# llrf_fmc_ext_male.net
KiCad netlist of a schematic drawn in Altium Designer
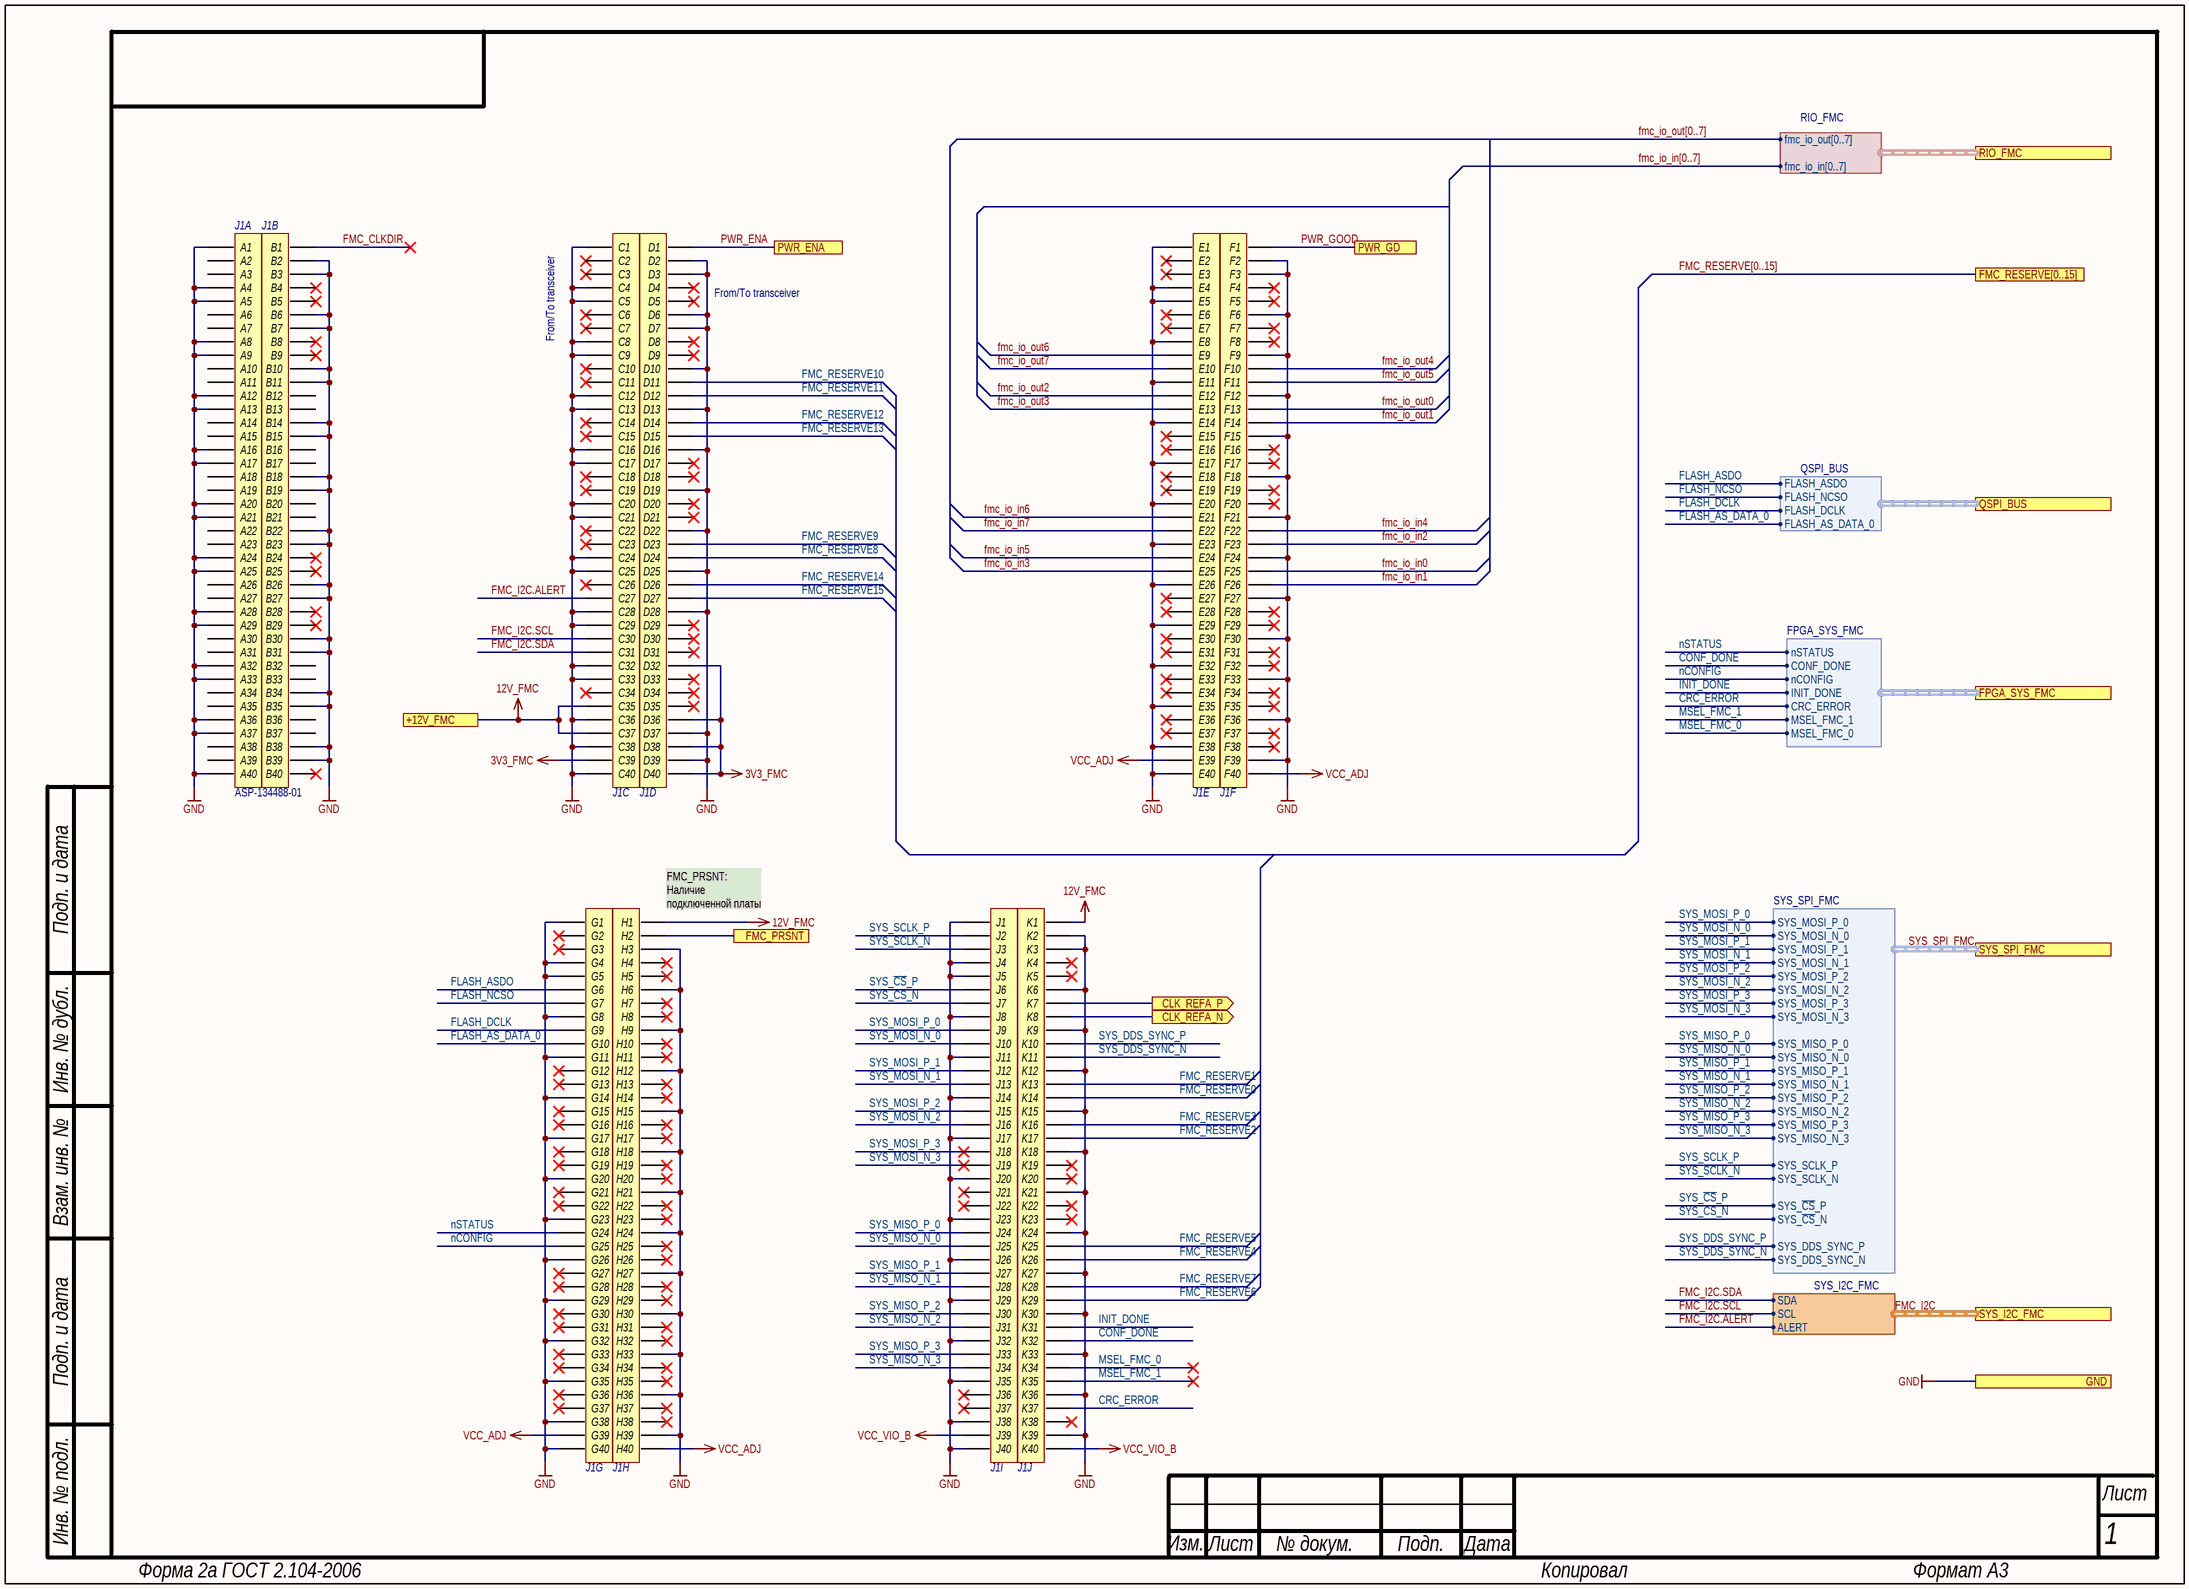
[diagram p0: llrf_fmc_ext_male.SchDoc]

(export (version "E")
  (design (tool "Eeschema 10.0.6"))
  (components
    (comp (ref "J1")
      (value "ASP-134488-01")
      (footprint "ASP-134488-01")
      (description "Socket Array Assembly, Surface Mount, 0.050\" Pitch, 400 Pins")
      (fields
        (field (name "MANUFACTURER") "SAMTEC")
        (field (name "НАИМЕНОВАНИЕ") "ASP-134488-01")
        (field (name "CREATED") "March 24, 2015 - Wendy Xin")
      )
      (libsource (lib "Connector") (part "ASP-134488-01"))
    )
  )
  (nets
    (net (code "6") (name "/CLK_REFA_N") (class "Default")
      (node (ref "J1") (pin "K8") (pinfunction "K8_K8") (pintype "passive"))
    )
    (net (code "7") (name "/CLK_REFA_P") (class "Default")
      (node (ref "J1") (pin "K7") (pinfunction "K7_K7") (pintype "passive"))
    )
    (net (code "8") (name "/CONF_DONE") (class "Default")
      (node (ref "J1") (pin "K32") (pinfunction "K32_K32") (pintype "passive"))
    )
    (net (code "9") (name "/CRC_ERROR") (class "Default")
      (node (ref "J1") (pin "K37") (pinfunction "K37_K37") (pintype "passive"))
    )
    (net (code "10") (name "/FLASH_ASDO") (class "Default")
      (node (ref "J1") (pin "G6") (pinfunction "G6_G6") (pintype "passive"))
    )
    (net (code "11") (name "/FLASH_AS_DATA_0") (class "Default")
      (node (ref "J1") (pin "G10") (pinfunction "G10_G10") (pintype "passive"))
    )
    (net (code "12") (name "/FLASH_DCLK") (class "Default")
      (node (ref "J1") (pin "G9") (pinfunction "G9_G9") (pintype "passive"))
    )
    (net (code "13") (name "/FLASH_NCSO") (class "Default")
      (node (ref "J1") (pin "G7") (pinfunction "G7_G7") (pintype "passive"))
    )
    (net (code "14") (name "/FMC_CLKDIR") (class "Default")
      (node (ref "J1") (pin "B1") (pinfunction "B1_B1") (pintype "passive+no_connect"))
    )
    (net (code "15") (name "/FMC_I2C.ALERT") (class "Default")
      (node (ref "J1") (pin "C27") (pinfunction "C27_C27") (pintype "passive"))
    )
    (net (code "16") (name "/FMC_I2C.SCL") (class "Default")
      (node (ref "J1") (pin "C30") (pinfunction "C30_C30") (pintype "passive"))
    )
    (net (code "17") (name "/FMC_I2C.SDA") (class "Default")
      (node (ref "J1") (pin "C31") (pinfunction "C31_C31") (pintype "passive"))
    )
    (net (code "19") (name "/FMC_PRSNT") (class "Default")
      (node (ref "J1") (pin "H2") (pinfunction "H2_H2") (pintype "passive"))
    )
    (net (code "20") (name "/FMC_RESERVE0") (class "Default")
      (node (ref "J1") (pin "K14") (pinfunction "K14_K14") (pintype "passive"))
    )
    (net (code "21") (name "/FMC_RESERVE1") (class "Default")
      (node (ref "J1") (pin "K13") (pinfunction "K13_K13") (pintype "passive"))
    )
    (net (code "22") (name "/FMC_RESERVE2") (class "Default")
      (node (ref "J1") (pin "K17") (pinfunction "K17_K17") (pintype "passive"))
    )
    (net (code "23") (name "/FMC_RESERVE3") (class "Default")
      (node (ref "J1") (pin "K16") (pinfunction "K16_K16") (pintype "passive"))
    )
    (net (code "24") (name "/FMC_RESERVE4") (class "Default")
      (node (ref "J1") (pin "K26") (pinfunction "K26_K26") (pintype "passive"))
    )
    (net (code "25") (name "/FMC_RESERVE5") (class "Default")
      (node (ref "J1") (pin "K25") (pinfunction "K25_K25") (pintype "passive"))
    )
    (net (code "26") (name "/FMC_RESERVE6") (class "Default")
      (node (ref "J1") (pin "K29") (pinfunction "K29_K29") (pintype "passive"))
    )
    (net (code "27") (name "/FMC_RESERVE7") (class "Default")
      (node (ref "J1") (pin "K28") (pinfunction "K28_K28") (pintype "passive"))
    )
    (net (code "28") (name "/FMC_RESERVE8") (class "Default")
      (node (ref "J1") (pin "D24") (pinfunction "D24_D24") (pintype "passive"))
    )
    (net (code "29") (name "/FMC_RESERVE9") (class "Default")
      (node (ref "J1") (pin "D23") (pinfunction "D23_D23") (pintype "passive"))
    )
    (net (code "30") (name "/FMC_RESERVE10") (class "Default")
      (node (ref "J1") (pin "D11") (pinfunction "D11_D11") (pintype "passive"))
    )
    (net (code "31") (name "/FMC_RESERVE11") (class "Default")
      (node (ref "J1") (pin "D12") (pinfunction "D12_D12") (pintype "passive"))
    )
    (net (code "32") (name "/FMC_RESERVE12") (class "Default")
      (node (ref "J1") (pin "D14") (pinfunction "D14_D14") (pintype "passive"))
    )
    (net (code "33") (name "/FMC_RESERVE13") (class "Default")
      (node (ref "J1") (pin "D15") (pinfunction "D15_D15") (pintype "passive"))
    )
    (net (code "34") (name "/FMC_RESERVE14") (class "Default")
      (node (ref "J1") (pin "D26") (pinfunction "D26_D26") (pintype "passive"))
    )
    (net (code "35") (name "/FMC_RESERVE15") (class "Default")
      (node (ref "J1") (pin "D27") (pinfunction "D27_D27") (pintype "passive"))
    )
    (net (code "37") (name "/INIT_DONE") (class "Default")
      (node (ref "J1") (pin "K31") (pinfunction "K31_K31") (pintype "passive"))
    )
    (net (code "38") (name "/MSEL_FMC_0") (class "Default")
      (node (ref "J1") (pin "K34") (pinfunction "K34_K34") (pintype "passive+no_connect"))
    )
    (net (code "39") (name "/MSEL_FMC_1") (class "Default")
      (node (ref "J1") (pin "K35") (pinfunction "K35_K35") (pintype "passive+no_connect"))
    )
    (net (code "40") (name "/PWR_ENA") (class "Default")
      (node (ref "J1") (pin "D1") (pinfunction "D1_D1") (pintype "passive"))
    )
    (net (code "41") (name "/PWR_GOOD") (class "Default")
      (node (ref "J1") (pin "F1") (pinfunction "F1_F1") (pintype "passive"))
    )
    (net (code "43") (name "/SYS_DDS_SYNC_N") (class "Default")
      (node (ref "J1") (pin "K11") (pinfunction "K11_K11") (pintype "passive"))
    )
    (net (code "44") (name "/SYS_DDS_SYNC_P") (class "Default")
      (node (ref "J1") (pin "K10") (pinfunction "K10_K10") (pintype "passive"))
    )
    (net (code "45") (name "/SYS_MISO_N_0") (class "Default")
      (node (ref "J1") (pin "J25") (pinfunction "J25_J25") (pintype "passive"))
    )
    (net (code "46") (name "/SYS_MISO_N_1") (class "Default")
      (node (ref "J1") (pin "J28") (pinfunction "J28_J28") (pintype "passive"))
    )
    (net (code "47") (name "/SYS_MISO_N_2") (class "Default")
      (node (ref "J1") (pin "J31") (pinfunction "J31_J31") (pintype "passive"))
    )
    (net (code "48") (name "/SYS_MISO_N_3") (class "Default")
      (node (ref "J1") (pin "J34") (pinfunction "J34_J34") (pintype "passive"))
    )
    (net (code "49") (name "/SYS_MISO_P_0") (class "Default")
      (node (ref "J1") (pin "J24") (pinfunction "J24_J24") (pintype "passive"))
    )
    (net (code "50") (name "/SYS_MISO_P_1") (class "Default")
      (node (ref "J1") (pin "J27") (pinfunction "J27_J27") (pintype "passive"))
    )
    (net (code "51") (name "/SYS_MISO_P_2") (class "Default")
      (node (ref "J1") (pin "J30") (pinfunction "J30_J30") (pintype "passive"))
    )
    (net (code "52") (name "/SYS_MISO_P_3") (class "Default")
      (node (ref "J1") (pin "J33") (pinfunction "J33_J33") (pintype "passive"))
    )
    (net (code "53") (name "/SYS_MOSI_N_0") (class "Default")
      (node (ref "J1") (pin "J10") (pinfunction "J10_J10") (pintype "passive"))
    )
    (net (code "54") (name "/SYS_MOSI_N_1") (class "Default")
      (node (ref "J1") (pin "J13") (pinfunction "J13_J13") (pintype "passive"))
    )
    (net (code "55") (name "/SYS_MOSI_N_2") (class "Default")
      (node (ref "J1") (pin "J16") (pinfunction "J16_J16") (pintype "passive"))
    )
    (net (code "56") (name "/SYS_MOSI_N_3") (class "Default")
      (node (ref "J1") (pin "J19") (pinfunction "J19_J19") (pintype "passive"))
    )
    (net (code "57") (name "/SYS_MOSI_P_0") (class "Default")
      (node (ref "J1") (pin "J9") (pinfunction "J9_J9") (pintype "passive"))
    )
    (net (code "58") (name "/SYS_MOSI_P_1") (class "Default")
      (node (ref "J1") (pin "J12") (pinfunction "J12_J12") (pintype "passive"))
    )
    (net (code "59") (name "/SYS_MOSI_P_2") (class "Default")
      (node (ref "J1") (pin "J15") (pinfunction "J15_J15") (pintype "passive"))
    )
    (net (code "60") (name "/SYS_MOSI_P_3") (class "Default")
      (node (ref "J1") (pin "J18") (pinfunction "J18_J18") (pintype "passive"))
    )
    (net (code "61") (name "/SYS_SCLK_N") (class "Default")
      (node (ref "J1") (pin "J3") (pinfunction "J3_J3") (pintype "passive"))
    )
    (net (code "62") (name "/SYS_SCLK_P") (class "Default")
      (node (ref "J1") (pin "J2") (pinfunction "J2_J2") (pintype "passive"))
    )
    (net (code "64") (name "/SYS_~{CS}_N") (class "Default")
      (node (ref "J1") (pin "J7") (pinfunction "J7_J7") (pintype "passive"))
    )
    (net (code "65") (name "/SYS_~{CS}_P") (class "Default")
      (node (ref "J1") (pin "J6") (pinfunction "J6_J6") (pintype "passive"))
    )
    (net (code "66") (name "/fmc_io_in0") (class "Default")
      (node (ref "J1") (pin "F25") (pinfunction "F25_F25") (pintype "passive"))
    )
    (net (code "67") (name "/fmc_io_in1") (class "Default")
      (node (ref "J1") (pin "F26") (pinfunction "F26_F26") (pintype "passive"))
    )
    (net (code "68") (name "/fmc_io_in2") (class "Default")
      (node (ref "J1") (pin "F23") (pinfunction "F23_F23") (pintype "passive"))
    )
    (net (code "69") (name "/fmc_io_in3") (class "Default")
      (node (ref "J1") (pin "E25") (pinfunction "E25_E25") (pintype "passive"))
    )
    (net (code "70") (name "/fmc_io_in4") (class "Default")
      (node (ref "J1") (pin "F22") (pinfunction "F22_F22") (pintype "passive"))
    )
    (net (code "71") (name "/fmc_io_in5") (class "Default")
      (node (ref "J1") (pin "E24") (pinfunction "E24_E24") (pintype "passive"))
    )
    (net (code "72") (name "/fmc_io_in6") (class "Default")
      (node (ref "J1") (pin "E21") (pinfunction "E21_E21") (pintype "passive"))
    )
    (net (code "73") (name "/fmc_io_in7") (class "Default")
      (node (ref "J1") (pin "E22") (pinfunction "E22_E22") (pintype "passive"))
    )
    (net (code "75") (name "/fmc_io_out0") (class "Default")
      (node (ref "J1") (pin "F13") (pinfunction "F13_F13") (pintype "passive"))
    )
    (net (code "76") (name "/fmc_io_out1") (class "Default")
      (node (ref "J1") (pin "F14") (pinfunction "F14_F14") (pintype "passive"))
    )
    (net (code "77") (name "/fmc_io_out2") (class "Default")
      (node (ref "J1") (pin "E12") (pinfunction "E12_E12") (pintype "passive"))
    )
    (net (code "78") (name "/fmc_io_out3") (class "Default")
      (node (ref "J1") (pin "E13") (pinfunction "E13_E13") (pintype "passive"))
    )
    (net (code "79") (name "/fmc_io_out4") (class "Default")
      (node (ref "J1") (pin "F10") (pinfunction "F10_F10") (pintype "passive"))
    )
    (net (code "80") (name "/fmc_io_out5") (class "Default")
      (node (ref "J1") (pin "F11") (pinfunction "F11_F11") (pintype "passive"))
    )
    (net (code "81") (name "/fmc_io_out6") (class "Default")
      (node (ref "J1") (pin "E9") (pinfunction "E9_E9") (pintype "passive"))
    )
    (net (code "82") (name "/fmc_io_out7") (class "Default")
      (node (ref "J1") (pin "E10") (pinfunction "E10_E10") (pintype "passive"))
    )
    (net (code "83") (name "/nCONFIG") (class "Default")
      (node (ref "J1") (pin "G25") (pinfunction "G25_G25") (pintype "passive"))
    )
    (net (code "84") (name "/nSTATUS") (class "Default")
      (node (ref "J1") (pin "G24") (pinfunction "G24_G24") (pintype "passive"))
    )
    (net (code "88") (name "3V3_FMC") (class "Default")
      (node (ref "J1") (pin "C39") (pinfunction "C39_C39") (pintype "passive"))
      (node (ref "J1") (pin "D32") (pinfunction "D32_D32") (pintype "passive"))
      (node (ref "J1") (pin "D36") (pinfunction "D36_D36") (pintype "passive"))
      (node (ref "J1") (pin "D38") (pinfunction "D38_D38") (pintype "passive"))
      (node (ref "J1") (pin "D40") (pinfunction "D40_D40") (pintype "passive"))
    )
    (net (code "89") (name "12V_FMC") (class "Default")
      (node (ref "J1") (pin "C35") (pinfunction "C35_C35") (pintype "passive"))
      (node (ref "J1") (pin "C37") (pinfunction "C37_C37") (pintype "passive"))
      (node (ref "J1") (pin "H1") (pinfunction "H1_H1") (pintype "passive"))
      (node (ref "J1") (pin "K1") (pinfunction "K1_K1") (pintype "passive"))
    )
    (net (code "90") (name "GND") (class "Default")
      (node (ref "J1") (pin "A1") (pinfunction "A1_A1") (pintype "passive"))
      (node (ref "J1") (pin "A12") (pinfunction "A12_A12") (pintype "passive"))
      (node (ref "J1") (pin "A13") (pinfunction "A13_A13") (pintype "passive"))
      (node (ref "J1") (pin "A16") (pinfunction "A16_A16") (pintype "passive"))
      (node (ref "J1") (pin "A17") (pinfunction "A17_A17") (pintype "passive"))
      (node (ref "J1") (pin "A20") (pinfunction "A20_A20") (pintype "passive"))
      (node (ref "J1") (pin "A21") (pinfunction "A21_A21") (pintype "passive"))
      (node (ref "J1") (pin "A24") (pinfunction "A24_A24") (pintype "passive"))
      (node (ref "J1") (pin "A25") (pinfunction "A25_A25") (pintype "passive"))
      (node (ref "J1") (pin "A28") (pinfunction "A28_A28") (pintype "passive"))
      (node (ref "J1") (pin "A29") (pinfunction "A29_A29") (pintype "passive"))
      (node (ref "J1") (pin "A32") (pinfunction "A32_A32") (pintype "passive"))
      (node (ref "J1") (pin "A33") (pinfunction "A33_A33") (pintype "passive"))
      (node (ref "J1") (pin "A36") (pinfunction "A36_A36") (pintype "passive"))
      (node (ref "J1") (pin "A37") (pinfunction "A37_A37") (pintype "passive"))
      (node (ref "J1") (pin "A4") (pinfunction "A4_A4") (pintype "passive"))
      (node (ref "J1") (pin "A40") (pinfunction "A40_A40") (pintype "passive"))
      (node (ref "J1") (pin "A5") (pinfunction "A5_A5") (pintype "passive"))
      (node (ref "J1") (pin "A8") (pinfunction "A8_A8") (pintype "passive"))
      (node (ref "J1") (pin "A9") (pinfunction "A9_A9") (pintype "passive"))
      (node (ref "J1") (pin "B10") (pinfunction "B10_B10") (pintype "passive"))
      (node (ref "J1") (pin "B11") (pinfunction "B11_B11") (pintype "passive"))
      (node (ref "J1") (pin "B14") (pinfunction "B14_B14") (pintype "passive"))
      (node (ref "J1") (pin "B15") (pinfunction "B15_B15") (pintype "passive"))
      (node (ref "J1") (pin "B18") (pinfunction "B18_B18") (pintype "passive"))
      (node (ref "J1") (pin "B19") (pinfunction "B19_B19") (pintype "passive"))
      (node (ref "J1") (pin "B2") (pinfunction "B2_B2") (pintype "passive"))
      (node (ref "J1") (pin "B22") (pinfunction "B22_B22") (pintype "passive"))
      (node (ref "J1") (pin "B23") (pinfunction "B23_B23") (pintype "passive"))
      (node (ref "J1") (pin "B26") (pinfunction "B26_B26") (pintype "passive"))
      (node (ref "J1") (pin "B27") (pinfunction "B27_B27") (pintype "passive"))
      (node (ref "J1") (pin "B3") (pinfunction "B3_B3") (pintype "passive"))
      (node (ref "J1") (pin "B30") (pinfunction "B30_B30") (pintype "passive"))
      (node (ref "J1") (pin "B31") (pinfunction "B31_B31") (pintype "passive"))
      (node (ref "J1") (pin "B34") (pinfunction "B34_B34") (pintype "passive"))
      (node (ref "J1") (pin "B35") (pinfunction "B35_B35") (pintype "passive"))
      (node (ref "J1") (pin "B38") (pinfunction "B38_B38") (pintype "passive"))
      (node (ref "J1") (pin "B39") (pinfunction "B39_B39") (pintype "passive"))
      (node (ref "J1") (pin "B6") (pinfunction "B6_B6") (pintype "passive"))
      (node (ref "J1") (pin "B7") (pinfunction "B7_B7") (pintype "passive"))
      (node (ref "J1") (pin "C1") (pinfunction "C1_C1") (pintype "passive"))
      (node (ref "J1") (pin "C12") (pinfunction "C12_C12") (pintype "passive"))
      (node (ref "J1") (pin "C13") (pinfunction "C13_C13") (pintype "passive"))
      (node (ref "J1") (pin "C16") (pinfunction "C16_C16") (pintype "passive"))
      (node (ref "J1") (pin "C17") (pinfunction "C17_C17") (pintype "passive"))
      (node (ref "J1") (pin "C20") (pinfunction "C20_C20") (pintype "passive"))
      (node (ref "J1") (pin "C21") (pinfunction "C21_C21") (pintype "passive"))
      (node (ref "J1") (pin "C24") (pinfunction "C24_C24") (pintype "passive"))
      (node (ref "J1") (pin "C25") (pinfunction "C25_C25") (pintype "passive"))
      (node (ref "J1") (pin "C28") (pinfunction "C28_C28") (pintype "passive"))
      (node (ref "J1") (pin "C29") (pinfunction "C29_C29") (pintype "passive"))
      (node (ref "J1") (pin "C32") (pinfunction "C32_C32") (pintype "passive"))
      (node (ref "J1") (pin "C33") (pinfunction "C33_C33") (pintype "passive"))
      (node (ref "J1") (pin "C36") (pinfunction "C36_C36") (pintype "passive"))
      (node (ref "J1") (pin "C38") (pinfunction "C38_C38") (pintype "passive"))
      (node (ref "J1") (pin "C4") (pinfunction "C4_C4") (pintype "passive"))
      (node (ref "J1") (pin "C40") (pinfunction "C40_C40") (pintype "passive"))
      (node (ref "J1") (pin "C5") (pinfunction "C5_C5") (pintype "passive"))
      (node (ref "J1") (pin "C8") (pinfunction "C8_C8") (pintype "passive"))
      (node (ref "J1") (pin "C9") (pinfunction "C9_C9") (pintype "passive"))
      (node (ref "J1") (pin "D10") (pinfunction "D10_D10") (pintype "passive"))
      (node (ref "J1") (pin "D13") (pinfunction "D13_D13") (pintype "passive"))
      (node (ref "J1") (pin "D16") (pinfunction "D16_D16") (pintype "passive"))
      (node (ref "J1") (pin "D19") (pinfunction "D19_D19") (pintype "passive"))
      (node (ref "J1") (pin "D2") (pinfunction "D2_D2") (pintype "passive"))
      (node (ref "J1") (pin "D22") (pinfunction "D22_D22") (pintype "passive"))
      (node (ref "J1") (pin "D25") (pinfunction "D25_D25") (pintype "passive"))
      (node (ref "J1") (pin "D28") (pinfunction "D28_D28") (pintype "passive"))
      (node (ref "J1") (pin "D3") (pinfunction "D3_D3") (pintype "passive"))
      (node (ref "J1") (pin "D37") (pinfunction "D37_D37") (pintype "passive"))
      (node (ref "J1") (pin "D39") (pinfunction "D39_D39") (pintype "passive"))
      (node (ref "J1") (pin "D6") (pinfunction "D6_D6") (pintype "passive"))
      (node (ref "J1") (pin "D7") (pinfunction "D7_D7") (pintype "passive"))
      (node (ref "J1") (pin "E1") (pinfunction "E1_E1") (pintype "passive"))
      (node (ref "J1") (pin "E11") (pinfunction "E11_E11") (pintype "passive"))
      (node (ref "J1") (pin "E14") (pinfunction "E14_E14") (pintype "passive"))
      (node (ref "J1") (pin "E17") (pinfunction "E17_E17") (pintype "passive"))
      (node (ref "J1") (pin "E20") (pinfunction "E20_E20") (pintype "passive"))
      (node (ref "J1") (pin "E23") (pinfunction "E23_E23") (pintype "passive"))
      (node (ref "J1") (pin "E26") (pinfunction "E26_E26") (pintype "passive"))
      (node (ref "J1") (pin "E29") (pinfunction "E29_E29") (pintype "passive"))
      (node (ref "J1") (pin "E32") (pinfunction "E32_E32") (pintype "passive"))
      (node (ref "J1") (pin "E35") (pinfunction "E35_E35") (pintype "passive"))
      (node (ref "J1") (pin "E38") (pinfunction "E38_E38") (pintype "passive"))
      (node (ref "J1") (pin "E4") (pinfunction "E4_E4") (pintype "passive"))
      (node (ref "J1") (pin "E40") (pinfunction "E40_E40") (pintype "passive"))
      (node (ref "J1") (pin "E5") (pinfunction "E5_E5") (pintype "passive"))
      (node (ref "J1") (pin "E8") (pinfunction "E8_E8") (pintype "passive"))
      (node (ref "J1") (pin "F12") (pinfunction "F12_F12") (pintype "passive"))
      (node (ref "J1") (pin "F15") (pinfunction "F15_F15") (pintype "passive"))
      (node (ref "J1") (pin "F18") (pinfunction "F18_F18") (pintype "passive"))
      (node (ref "J1") (pin "F2") (pinfunction "F2_F2") (pintype "passive"))
      (node (ref "J1") (pin "F21") (pinfunction "F21_F21") (pintype "passive"))
      (node (ref "J1") (pin "F24") (pinfunction "F24_F24") (pintype "passive"))
      (node (ref "J1") (pin "F27") (pinfunction "F27_F27") (pintype "passive"))
      (node (ref "J1") (pin "F3") (pinfunction "F3_F3") (pintype "passive"))
      (node (ref "J1") (pin "F30") (pinfunction "F30_F30") (pintype "passive"))
      (node (ref "J1") (pin "F33") (pinfunction "F33_F33") (pintype "passive"))
      (node (ref "J1") (pin "F36") (pinfunction "F36_F36") (pintype "passive"))
      (node (ref "J1") (pin "F39") (pinfunction "F39_F39") (pintype "passive"))
      (node (ref "J1") (pin "F6") (pinfunction "F6_F6") (pintype "passive"))
      (node (ref "J1") (pin "F9") (pinfunction "F9_F9") (pintype "passive"))
      (node (ref "J1") (pin "G1") (pinfunction "G1_G1") (pintype "passive"))
      (node (ref "J1") (pin "G11") (pinfunction "G11_G11") (pintype "passive"))
      (node (ref "J1") (pin "G14") (pinfunction "G14_G14") (pintype "passive"))
      (node (ref "J1") (pin "G17") (pinfunction "G17_G17") (pintype "passive"))
      (node (ref "J1") (pin "G20") (pinfunction "G20_G20") (pintype "passive"))
      (node (ref "J1") (pin "G23") (pinfunction "G23_G23") (pintype "passive"))
      (node (ref "J1") (pin "G26") (pinfunction "G26_G26") (pintype "passive"))
      (node (ref "J1") (pin "G29") (pinfunction "G29_G29") (pintype "passive"))
      (node (ref "J1") (pin "G32") (pinfunction "G32_G32") (pintype "passive"))
      (node (ref "J1") (pin "G35") (pinfunction "G35_G35") (pintype "passive"))
      (node (ref "J1") (pin "G38") (pinfunction "G38_G38") (pintype "passive"))
      (node (ref "J1") (pin "G4") (pinfunction "G4_G4") (pintype "passive"))
      (node (ref "J1") (pin "G40") (pinfunction "G40_G40") (pintype "passive"))
      (node (ref "J1") (pin "G5") (pinfunction "G5_G5") (pintype "passive"))
      (node (ref "J1") (pin "G8") (pinfunction "G8_G8") (pintype "passive"))
      (node (ref "J1") (pin "H12") (pinfunction "H12_H12") (pintype "passive"))
      (node (ref "J1") (pin "H15") (pinfunction "H15_H15") (pintype "passive"))
      (node (ref "J1") (pin "H18") (pinfunction "H18_H18") (pintype "passive"))
      (node (ref "J1") (pin "H21") (pinfunction "H21_H21") (pintype "passive"))
      (node (ref "J1") (pin "H24") (pinfunction "H24_H24") (pintype "passive"))
      (node (ref "J1") (pin "H27") (pinfunction "H27_H27") (pintype "passive"))
      (node (ref "J1") (pin "H3") (pinfunction "H3_H3") (pintype "passive"))
      (node (ref "J1") (pin "H30") (pinfunction "H30_H30") (pintype "passive"))
      (node (ref "J1") (pin "H33") (pinfunction "H33_H33") (pintype "passive"))
      (node (ref "J1") (pin "H36") (pinfunction "H36_H36") (pintype "passive"))
      (node (ref "J1") (pin "H39") (pinfunction "H39_H39") (pintype "passive"))
      (node (ref "J1") (pin "H6") (pinfunction "H6_H6") (pintype "passive"))
      (node (ref "J1") (pin "H9") (pinfunction "H9_H9") (pintype "passive"))
      (node (ref "J1") (pin "J1") (pinfunction "J1_J1") (pintype "passive"))
      (node (ref "J1") (pin "J11") (pinfunction "J11_J11") (pintype "passive"))
      (node (ref "J1") (pin "J14") (pinfunction "J14_J14") (pintype "passive"))
      (node (ref "J1") (pin "J17") (pinfunction "J17_J17") (pintype "passive"))
      (node (ref "J1") (pin "J20") (pinfunction "J20_J20") (pintype "passive"))
      (node (ref "J1") (pin "J23") (pinfunction "J23_J23") (pintype "passive"))
      (node (ref "J1") (pin "J26") (pinfunction "J26_J26") (pintype "passive"))
      (node (ref "J1") (pin "J29") (pinfunction "J29_J29") (pintype "passive"))
      (node (ref "J1") (pin "J32") (pinfunction "J32_J32") (pintype "passive"))
      (node (ref "J1") (pin "J35") (pinfunction "J35_J35") (pintype "passive"))
      (node (ref "J1") (pin "J38") (pinfunction "J38_J38") (pintype "passive"))
      (node (ref "J1") (pin "J4") (pinfunction "J4_J4") (pintype "passive"))
      (node (ref "J1") (pin "J40") (pinfunction "J40_J40") (pintype "passive"))
      (node (ref "J1") (pin "J5") (pinfunction "J5_J5") (pintype "passive"))
      (node (ref "J1") (pin "J8") (pinfunction "J8_J8") (pintype "passive"))
      (node (ref "J1") (pin "K12") (pinfunction "K12_K12") (pintype "passive"))
      (node (ref "J1") (pin "K15") (pinfunction "K15_K15") (pintype "passive"))
      (node (ref "J1") (pin "K18") (pinfunction "K18_K18") (pintype "passive"))
      (node (ref "J1") (pin "K2") (pinfunction "K2_K2") (pintype "passive"))
      (node (ref "J1") (pin "K21") (pinfunction "K21_K21") (pintype "passive"))
      (node (ref "J1") (pin "K24") (pinfunction "K24_K24") (pintype "passive"))
      (node (ref "J1") (pin "K27") (pinfunction "K27_K27") (pintype "passive"))
      (node (ref "J1") (pin "K3") (pinfunction "K3_K3") (pintype "passive"))
      (node (ref "J1") (pin "K30") (pinfunction "K30_K30") (pintype "passive"))
      (node (ref "J1") (pin "K33") (pinfunction "K33_K33") (pintype "passive"))
      (node (ref "J1") (pin "K36") (pinfunction "K36_K36") (pintype "passive"))
      (node (ref "J1") (pin "K39") (pinfunction "K39_K39") (pintype "passive"))
      (node (ref "J1") (pin "K6") (pinfunction "K6_K6") (pintype "passive"))
      (node (ref "J1") (pin "K9") (pinfunction "K9_K9") (pintype "passive"))
    )
    (net (code "91") (name "VCC_ADJ") (class "Default")
      (node (ref "J1") (pin "E39") (pinfunction "E39_E39") (pintype "passive"))
      (node (ref "J1") (pin "F40") (pinfunction "F40_F40") (pintype "passive"))
      (node (ref "J1") (pin "G39") (pinfunction "G39_G39") (pintype "passive"))
      (node (ref "J1") (pin "H40") (pinfunction "H40_H40") (pintype "passive"))
    )
    (net (code "92") (name "VCC_VIO_B") (class "Default")
      (node (ref "J1") (pin "J39") (pinfunction "J39_J39") (pintype "passive"))
      (node (ref "J1") (pin "K40") (pinfunction "K40_K40") (pintype "passive"))
    )
    (net (code "93") (name "unconnected-(J1-PadA2)") (class "Default")
      (node (ref "J1") (pin "A2") (pinfunction "A2_A2") (pintype "passive"))
    )
    (net (code "94") (name "unconnected-(J1-PadA3)") (class "Default")
      (node (ref "J1") (pin "A3") (pinfunction "A3_A3") (pintype "passive"))
    )
    (net (code "95") (name "unconnected-(J1-PadA6)") (class "Default")
      (node (ref "J1") (pin "A6") (pinfunction "A6_A6") (pintype "passive"))
    )
    (net (code "96") (name "unconnected-(J1-PadA7)") (class "Default")
      (node (ref "J1") (pin "A7") (pinfunction "A7_A7") (pintype "passive"))
    )
    (net (code "97") (name "unconnected-(J1-PadA10)") (class "Default")
      (node (ref "J1") (pin "A10") (pinfunction "A10_A10") (pintype "passive"))
    )
    (net (code "98") (name "unconnected-(J1-PadA11)") (class "Default")
      (node (ref "J1") (pin "A11") (pinfunction "A11_A11") (pintype "passive"))
    )
    (net (code "99") (name "unconnected-(J1-PadA14)") (class "Default")
      (node (ref "J1") (pin "A14") (pinfunction "A14_A14") (pintype "passive"))
    )
    (net (code "100") (name "unconnected-(J1-PadA15)") (class "Default")
      (node (ref "J1") (pin "A15") (pinfunction "A15_A15") (pintype "passive"))
    )
    (net (code "101") (name "unconnected-(J1-PadA18)") (class "Default")
      (node (ref "J1") (pin "A18") (pinfunction "A18_A18") (pintype "passive"))
    )
    (net (code "102") (name "unconnected-(J1-PadA19)") (class "Default")
      (node (ref "J1") (pin "A19") (pinfunction "A19_A19") (pintype "passive"))
    )
    (net (code "103") (name "unconnected-(J1-PadA22)") (class "Default")
      (node (ref "J1") (pin "A22") (pinfunction "A22_A22") (pintype "passive"))
    )
    (net (code "104") (name "unconnected-(J1-PadA23)") (class "Default")
      (node (ref "J1") (pin "A23") (pinfunction "A23_A23") (pintype "passive"))
    )
    (net (code "105") (name "unconnected-(J1-PadA26)") (class "Default")
      (node (ref "J1") (pin "A26") (pinfunction "A26_A26") (pintype "passive"))
    )
    (net (code "106") (name "unconnected-(J1-PadA27)") (class "Default")
      (node (ref "J1") (pin "A27") (pinfunction "A27_A27") (pintype "passive"))
    )
    (net (code "107") (name "unconnected-(J1-PadA30)") (class "Default")
      (node (ref "J1") (pin "A30") (pinfunction "A30_A30") (pintype "passive"))
    )
    (net (code "108") (name "unconnected-(J1-PadA31)") (class "Default")
      (node (ref "J1") (pin "A31") (pinfunction "A31_A31") (pintype "passive"))
    )
    (net (code "109") (name "unconnected-(J1-PadA34)") (class "Default")
      (node (ref "J1") (pin "A34") (pinfunction "A34_A34") (pintype "passive"))
    )
    (net (code "110") (name "unconnected-(J1-PadA35)") (class "Default")
      (node (ref "J1") (pin "A35") (pinfunction "A35_A35") (pintype "passive"))
    )
    (net (code "111") (name "unconnected-(J1-PadA38)") (class "Default")
      (node (ref "J1") (pin "A38") (pinfunction "A38_A38") (pintype "passive"))
    )
    (net (code "112") (name "unconnected-(J1-PadA39)") (class "Default")
      (node (ref "J1") (pin "A39") (pinfunction "A39_A39") (pintype "passive"))
    )
    (net (code "113") (name "unconnected-(J1-PadB4)") (class "Default")
      (node (ref "J1") (pin "B4") (pinfunction "B4_B4") (pintype "passive+no_connect"))
    )
    (net (code "114") (name "unconnected-(J1-PadB5)") (class "Default")
      (node (ref "J1") (pin "B5") (pinfunction "B5_B5") (pintype "passive+no_connect"))
    )
    (net (code "115") (name "unconnected-(J1-PadB8)") (class "Default")
      (node (ref "J1") (pin "B8") (pinfunction "B8_B8") (pintype "passive+no_connect"))
    )
    (net (code "116") (name "unconnected-(J1-PadB9)") (class "Default")
      (node (ref "J1") (pin "B9") (pinfunction "B9_B9") (pintype "passive+no_connect"))
    )
    (net (code "117") (name "unconnected-(J1-PadB12)") (class "Default")
      (node (ref "J1") (pin "B12") (pinfunction "B12_B12") (pintype "passive"))
    )
    (net (code "118") (name "unconnected-(J1-PadB13)") (class "Default")
      (node (ref "J1") (pin "B13") (pinfunction "B13_B13") (pintype "passive"))
    )
    (net (code "119") (name "unconnected-(J1-PadB16)") (class "Default")
      (node (ref "J1") (pin "B16") (pinfunction "B16_B16") (pintype "passive"))
    )
    (net (code "120") (name "unconnected-(J1-PadB17)") (class "Default")
      (node (ref "J1") (pin "B17") (pinfunction "B17_B17") (pintype "passive"))
    )
    (net (code "121") (name "unconnected-(J1-PadB20)") (class "Default")
      (node (ref "J1") (pin "B20") (pinfunction "B20_B20") (pintype "passive"))
    )
    (net (code "122") (name "unconnected-(J1-PadB21)") (class "Default")
      (node (ref "J1") (pin "B21") (pinfunction "B21_B21") (pintype "passive"))
    )
    (net (code "123") (name "unconnected-(J1-PadB24)") (class "Default")
      (node (ref "J1") (pin "B24") (pinfunction "B24_B24") (pintype "passive+no_connect"))
    )
    (net (code "124") (name "unconnected-(J1-PadB25)") (class "Default")
      (node (ref "J1") (pin "B25") (pinfunction "B25_B25") (pintype "passive+no_connect"))
    )
    (net (code "125") (name "unconnected-(J1-PadB28)") (class "Default")
      (node (ref "J1") (pin "B28") (pinfunction "B28_B28") (pintype "passive+no_connect"))
    )
    (net (code "126") (name "unconnected-(J1-PadB29)") (class "Default")
      (node (ref "J1") (pin "B29") (pinfunction "B29_B29") (pintype "passive+no_connect"))
    )
    (net (code "127") (name "unconnected-(J1-PadB32)") (class "Default")
      (node (ref "J1") (pin "B32") (pinfunction "B32_B32") (pintype "passive"))
    )
    (net (code "128") (name "unconnected-(J1-PadB33)") (class "Default")
      (node (ref "J1") (pin "B33") (pinfunction "B33_B33") (pintype "passive"))
    )
    (net (code "129") (name "unconnected-(J1-PadB36)") (class "Default")
      (node (ref "J1") (pin "B36") (pinfunction "B36_B36") (pintype "passive"))
    )
    (net (code "130") (name "unconnected-(J1-PadB37)") (class "Default")
      (node (ref "J1") (pin "B37") (pinfunction "B37_B37") (pintype "passive"))
    )
    (net (code "131") (name "unconnected-(J1-PadB40)") (class "Default")
      (node (ref "J1") (pin "B40") (pinfunction "B40_B40") (pintype "passive+no_connect"))
    )
    (net (code "132") (name "unconnected-(J1-PadC2)") (class "Default")
      (node (ref "J1") (pin "C2") (pinfunction "C2_C2") (pintype "passive+no_connect"))
    )
    (net (code "133") (name "unconnected-(J1-PadC3)") (class "Default")
      (node (ref "J1") (pin "C3") (pinfunction "C3_C3") (pintype "passive+no_connect"))
    )
    (net (code "134") (name "unconnected-(J1-PadC6)") (class "Default")
      (node (ref "J1") (pin "C6") (pinfunction "C6_C6") (pintype "passive+no_connect"))
    )
    (net (code "135") (name "unconnected-(J1-PadC7)") (class "Default")
      (node (ref "J1") (pin "C7") (pinfunction "C7_C7") (pintype "passive+no_connect"))
    )
    (net (code "136") (name "unconnected-(J1-PadC10)") (class "Default")
      (node (ref "J1") (pin "C10") (pinfunction "C10_C10") (pintype "passive+no_connect"))
    )
    (net (code "137") (name "unconnected-(J1-PadC11)") (class "Default")
      (node (ref "J1") (pin "C11") (pinfunction "C11_C11") (pintype "passive+no_connect"))
    )
    (net (code "138") (name "unconnected-(J1-PadC14)") (class "Default")
      (node (ref "J1") (pin "C14") (pinfunction "C14_C14") (pintype "passive+no_connect"))
    )
    (net (code "139") (name "unconnected-(J1-PadC15)") (class "Default")
      (node (ref "J1") (pin "C15") (pinfunction "C15_C15") (pintype "passive+no_connect"))
    )
    (net (code "140") (name "unconnected-(J1-PadC18)") (class "Default")
      (node (ref "J1") (pin "C18") (pinfunction "C18_C18") (pintype "passive+no_connect"))
    )
    (net (code "141") (name "unconnected-(J1-PadC19)") (class "Default")
      (node (ref "J1") (pin "C19") (pinfunction "C19_C19") (pintype "passive+no_connect"))
    )
    (net (code "142") (name "unconnected-(J1-PadC22)") (class "Default")
      (node (ref "J1") (pin "C22") (pinfunction "C22_C22") (pintype "passive+no_connect"))
    )
    (net (code "143") (name "unconnected-(J1-PadC23)") (class "Default")
      (node (ref "J1") (pin "C23") (pinfunction "C23_C23") (pintype "passive+no_connect"))
    )
    (net (code "144") (name "unconnected-(J1-PadC26)") (class "Default")
      (node (ref "J1") (pin "C26") (pinfunction "C26_C26") (pintype "passive+no_connect"))
    )
    (net (code "145") (name "unconnected-(J1-PadC34)") (class "Default")
      (node (ref "J1") (pin "C34") (pinfunction "C34_C34") (pintype "passive+no_connect"))
    )
    (net (code "146") (name "unconnected-(J1-PadD4)") (class "Default")
      (node (ref "J1") (pin "D4") (pinfunction "D4_D4") (pintype "passive+no_connect"))
    )
    (net (code "147") (name "unconnected-(J1-PadD5)") (class "Default")
      (node (ref "J1") (pin "D5") (pinfunction "D5_D5") (pintype "passive+no_connect"))
    )
    (net (code "148") (name "unconnected-(J1-PadD8)") (class "Default")
      (node (ref "J1") (pin "D8") (pinfunction "D8_D8") (pintype "passive+no_connect"))
    )
    (net (code "149") (name "unconnected-(J1-PadD9)") (class "Default")
      (node (ref "J1") (pin "D9") (pinfunction "D9_D9") (pintype "passive+no_connect"))
    )
    (net (code "150") (name "unconnected-(J1-PadD17)") (class "Default")
      (node (ref "J1") (pin "D17") (pinfunction "D17_D17") (pintype "passive+no_connect"))
    )
    (net (code "151") (name "unconnected-(J1-PadD18)") (class "Default")
      (node (ref "J1") (pin "D18") (pinfunction "D18_D18") (pintype "passive+no_connect"))
    )
    (net (code "152") (name "unconnected-(J1-PadD20)") (class "Default")
      (node (ref "J1") (pin "D20") (pinfunction "D20_D20") (pintype "passive+no_connect"))
    )
    (net (code "153") (name "unconnected-(J1-PadD21)") (class "Default")
      (node (ref "J1") (pin "D21") (pinfunction "D21_D21") (pintype "passive+no_connect"))
    )
    (net (code "154") (name "unconnected-(J1-PadD29)") (class "Default")
      (node (ref "J1") (pin "D29") (pinfunction "D29_D29") (pintype "passive+no_connect"))
    )
    (net (code "155") (name "unconnected-(J1-PadD30)") (class "Default")
      (node (ref "J1") (pin "D30") (pinfunction "D30_D30") (pintype "passive+no_connect"))
    )
    (net (code "156") (name "unconnected-(J1-PadD31)") (class "Default")
      (node (ref "J1") (pin "D31") (pinfunction "D31_D31") (pintype "passive+no_connect"))
    )
    (net (code "157") (name "unconnected-(J1-PadD33)") (class "Default")
      (node (ref "J1") (pin "D33") (pinfunction "D33_D33") (pintype "passive+no_connect"))
    )
    (net (code "158") (name "unconnected-(J1-PadD34)") (class "Default")
      (node (ref "J1") (pin "D34") (pinfunction "D34_D34") (pintype "passive+no_connect"))
    )
    (net (code "159") (name "unconnected-(J1-PadD35)") (class "Default")
      (node (ref "J1") (pin "D35") (pinfunction "D35_D35") (pintype "passive+no_connect"))
    )
    (net (code "160") (name "unconnected-(J1-PadE2)") (class "Default")
      (node (ref "J1") (pin "E2") (pinfunction "E2_E2") (pintype "passive+no_connect"))
    )
    (net (code "161") (name "unconnected-(J1-PadE3)") (class "Default")
      (node (ref "J1") (pin "E3") (pinfunction "E3_E3") (pintype "passive+no_connect"))
    )
    (net (code "162") (name "unconnected-(J1-PadE6)") (class "Default")
      (node (ref "J1") (pin "E6") (pinfunction "E6_E6") (pintype "passive+no_connect"))
    )
    (net (code "163") (name "unconnected-(J1-PadE7)") (class "Default")
      (node (ref "J1") (pin "E7") (pinfunction "E7_E7") (pintype "passive+no_connect"))
    )
    (net (code "164") (name "unconnected-(J1-PadE15)") (class "Default")
      (node (ref "J1") (pin "E15") (pinfunction "E15_E15") (pintype "passive+no_connect"))
    )
    (net (code "165") (name "unconnected-(J1-PadE16)") (class "Default")
      (node (ref "J1") (pin "E16") (pinfunction "E16_E16") (pintype "passive+no_connect"))
    )
    (net (code "166") (name "unconnected-(J1-PadE18)") (class "Default")
      (node (ref "J1") (pin "E18") (pinfunction "E18_E18") (pintype "passive+no_connect"))
    )
    (net (code "167") (name "unconnected-(J1-PadE19)") (class "Default")
      (node (ref "J1") (pin "E19") (pinfunction "E19_E19") (pintype "passive+no_connect"))
    )
    (net (code "168") (name "unconnected-(J1-PadE27)") (class "Default")
      (node (ref "J1") (pin "E27") (pinfunction "E27_E27") (pintype "passive+no_connect"))
    )
    (net (code "169") (name "unconnected-(J1-PadE28)") (class "Default")
      (node (ref "J1") (pin "E28") (pinfunction "E28_E28") (pintype "passive+no_connect"))
    )
    (net (code "170") (name "unconnected-(J1-PadE30)") (class "Default")
      (node (ref "J1") (pin "E30") (pinfunction "E30_E30") (pintype "passive+no_connect"))
    )
    (net (code "171") (name "unconnected-(J1-PadE31)") (class "Default")
      (node (ref "J1") (pin "E31") (pinfunction "E31_E31") (pintype "passive+no_connect"))
    )
    (net (code "172") (name "unconnected-(J1-PadE33)") (class "Default")
      (node (ref "J1") (pin "E33") (pinfunction "E33_E33") (pintype "passive+no_connect"))
    )
    (net (code "173") (name "unconnected-(J1-PadE34)") (class "Default")
      (node (ref "J1") (pin "E34") (pinfunction "E34_E34") (pintype "passive+no_connect"))
    )
    (net (code "174") (name "unconnected-(J1-PadE36)") (class "Default")
      (node (ref "J1") (pin "E36") (pinfunction "E36_E36") (pintype "passive+no_connect"))
    )
    (net (code "175") (name "unconnected-(J1-PadE37)") (class "Default")
      (node (ref "J1") (pin "E37") (pinfunction "E37_E37") (pintype "passive+no_connect"))
    )
    (net (code "176") (name "unconnected-(J1-PadF4)") (class "Default")
      (node (ref "J1") (pin "F4") (pinfunction "F4_F4") (pintype "passive+no_connect"))
    )
    (net (code "177") (name "unconnected-(J1-PadF5)") (class "Default")
      (node (ref "J1") (pin "F5") (pinfunction "F5_F5") (pintype "passive+no_connect"))
    )
    (net (code "178") (name "unconnected-(J1-PadF7)") (class "Default")
      (node (ref "J1") (pin "F7") (pinfunction "F7_F7") (pintype "passive+no_connect"))
    )
    (net (code "179") (name "unconnected-(J1-PadF8)") (class "Default")
      (node (ref "J1") (pin "F8") (pinfunction "F8_F8") (pintype "passive+no_connect"))
    )
    (net (code "180") (name "unconnected-(J1-PadF16)") (class "Default")
      (node (ref "J1") (pin "F16") (pinfunction "F16_F16") (pintype "passive+no_connect"))
    )
    (net (code "181") (name "unconnected-(J1-PadF17)") (class "Default")
      (node (ref "J1") (pin "F17") (pinfunction "F17_F17") (pintype "passive+no_connect"))
    )
    (net (code "182") (name "unconnected-(J1-PadF19)") (class "Default")
      (node (ref "J1") (pin "F19") (pinfunction "F19_F19") (pintype "passive+no_connect"))
    )
    (net (code "183") (name "unconnected-(J1-PadF20)") (class "Default")
      (node (ref "J1") (pin "F20") (pinfunction "F20_F20") (pintype "passive+no_connect"))
    )
    (net (code "184") (name "unconnected-(J1-PadF28)") (class "Default")
      (node (ref "J1") (pin "F28") (pinfunction "F28_F28") (pintype "passive+no_connect"))
    )
    (net (code "185") (name "unconnected-(J1-PadF29)") (class "Default")
      (node (ref "J1") (pin "F29") (pinfunction "F29_F29") (pintype "passive+no_connect"))
    )
    (net (code "186") (name "unconnected-(J1-PadF31)") (class "Default")
      (node (ref "J1") (pin "F31") (pinfunction "F31_F31") (pintype "passive+no_connect"))
    )
    (net (code "187") (name "unconnected-(J1-PadF32)") (class "Default")
      (node (ref "J1") (pin "F32") (pinfunction "F32_F32") (pintype "passive+no_connect"))
    )
    (net (code "188") (name "unconnected-(J1-PadF34)") (class "Default")
      (node (ref "J1") (pin "F34") (pinfunction "F34_F34") (pintype "passive+no_connect"))
    )
    (net (code "189") (name "unconnected-(J1-PadF35)") (class "Default")
      (node (ref "J1") (pin "F35") (pinfunction "F35_F35") (pintype "passive+no_connect"))
    )
    (net (code "190") (name "unconnected-(J1-PadF37)") (class "Default")
      (node (ref "J1") (pin "F37") (pinfunction "F37_F37") (pintype "passive+no_connect"))
    )
    (net (code "191") (name "unconnected-(J1-PadF38)") (class "Default")
      (node (ref "J1") (pin "F38") (pinfunction "F38_F38") (pintype "passive+no_connect"))
    )
    (net (code "192") (name "unconnected-(J1-PadG2)") (class "Default")
      (node (ref "J1") (pin "G2") (pinfunction "G2_G2") (pintype "passive+no_connect"))
    )
    (net (code "193") (name "unconnected-(J1-PadG3)") (class "Default")
      (node (ref "J1") (pin "G3") (pinfunction "G3_G3") (pintype "passive+no_connect"))
    )
    (net (code "194") (name "unconnected-(J1-PadG12)") (class "Default")
      (node (ref "J1") (pin "G12") (pinfunction "G12_G12") (pintype "passive+no_connect"))
    )
    (net (code "195") (name "unconnected-(J1-PadG13)") (class "Default")
      (node (ref "J1") (pin "G13") (pinfunction "G13_G13") (pintype "passive+no_connect"))
    )
    (net (code "196") (name "unconnected-(J1-PadG15)") (class "Default")
      (node (ref "J1") (pin "G15") (pinfunction "G15_G15") (pintype "passive+no_connect"))
    )
    (net (code "197") (name "unconnected-(J1-PadG16)") (class "Default")
      (node (ref "J1") (pin "G16") (pinfunction "G16_G16") (pintype "passive+no_connect"))
    )
    (net (code "198") (name "unconnected-(J1-PadG18)") (class "Default")
      (node (ref "J1") (pin "G18") (pinfunction "G18_G18") (pintype "passive+no_connect"))
    )
    (net (code "199") (name "unconnected-(J1-PadG19)") (class "Default")
      (node (ref "J1") (pin "G19") (pinfunction "G19_G19") (pintype "passive+no_connect"))
    )
    (net (code "200") (name "unconnected-(J1-PadG21)") (class "Default")
      (node (ref "J1") (pin "G21") (pinfunction "G21_G21") (pintype "passive+no_connect"))
    )
    (net (code "201") (name "unconnected-(J1-PadG22)") (class "Default")
      (node (ref "J1") (pin "G22") (pinfunction "G22_G22") (pintype "passive+no_connect"))
    )
    (net (code "202") (name "unconnected-(J1-PadG27)") (class "Default")
      (node (ref "J1") (pin "G27") (pinfunction "G27_G27") (pintype "passive+no_connect"))
    )
    (net (code "203") (name "unconnected-(J1-PadG28)") (class "Default")
      (node (ref "J1") (pin "G28") (pinfunction "G28_G28") (pintype "passive+no_connect"))
    )
    (net (code "204") (name "unconnected-(J1-PadG30)") (class "Default")
      (node (ref "J1") (pin "G30") (pinfunction "G30_G30") (pintype "passive+no_connect"))
    )
    (net (code "205") (name "unconnected-(J1-PadG31)") (class "Default")
      (node (ref "J1") (pin "G31") (pinfunction "G31_G31") (pintype "passive+no_connect"))
    )
    (net (code "206") (name "unconnected-(J1-PadG33)") (class "Default")
      (node (ref "J1") (pin "G33") (pinfunction "G33_G33") (pintype "passive+no_connect"))
    )
    (net (code "207") (name "unconnected-(J1-PadG34)") (class "Default")
      (node (ref "J1") (pin "G34") (pinfunction "G34_G34") (pintype "passive+no_connect"))
    )
    (net (code "208") (name "unconnected-(J1-PadG36)") (class "Default")
      (node (ref "J1") (pin "G36") (pinfunction "G36_G36") (pintype "passive+no_connect"))
    )
    (net (code "209") (name "unconnected-(J1-PadG37)") (class "Default")
      (node (ref "J1") (pin "G37") (pinfunction "G37_G37") (pintype "passive+no_connect"))
    )
    (net (code "210") (name "unconnected-(J1-PadH4)") (class "Default")
      (node (ref "J1") (pin "H4") (pinfunction "H4_H4") (pintype "passive+no_connect"))
    )
    (net (code "211") (name "unconnected-(J1-PadH5)") (class "Default")
      (node (ref "J1") (pin "H5") (pinfunction "H5_H5") (pintype "passive+no_connect"))
    )
    (net (code "212") (name "unconnected-(J1-PadH7)") (class "Default")
      (node (ref "J1") (pin "H7") (pinfunction "H7_H7") (pintype "passive+no_connect"))
    )
    (net (code "213") (name "unconnected-(J1-PadH8)") (class "Default")
      (node (ref "J1") (pin "H8") (pinfunction "H8_H8") (pintype "passive+no_connect"))
    )
    (net (code "214") (name "unconnected-(J1-PadH10)") (class "Default")
      (node (ref "J1") (pin "H10") (pinfunction "H10_H10") (pintype "passive+no_connect"))
    )
    (net (code "215") (name "unconnected-(J1-PadH11)") (class "Default")
      (node (ref "J1") (pin "H11") (pinfunction "H11_H11") (pintype "passive+no_connect"))
    )
    (net (code "216") (name "unconnected-(J1-PadH13)") (class "Default")
      (node (ref "J1") (pin "H13") (pinfunction "H13_H13") (pintype "passive+no_connect"))
    )
    (net (code "217") (name "unconnected-(J1-PadH14)") (class "Default")
      (node (ref "J1") (pin "H14") (pinfunction "H14_H14") (pintype "passive+no_connect"))
    )
    (net (code "218") (name "unconnected-(J1-PadH16)") (class "Default")
      (node (ref "J1") (pin "H16") (pinfunction "H16_H16") (pintype "passive+no_connect"))
    )
    (net (code "219") (name "unconnected-(J1-PadH17)") (class "Default")
      (node (ref "J1") (pin "H17") (pinfunction "H17_H17") (pintype "passive+no_connect"))
    )
    (net (code "220") (name "unconnected-(J1-PadH19)") (class "Default")
      (node (ref "J1") (pin "H19") (pinfunction "H19_H19") (pintype "passive+no_connect"))
    )
    (net (code "221") (name "unconnected-(J1-PadH20)") (class "Default")
      (node (ref "J1") (pin "H20") (pinfunction "H20_H20") (pintype "passive+no_connect"))
    )
    (net (code "222") (name "unconnected-(J1-PadH22)") (class "Default")
      (node (ref "J1") (pin "H22") (pinfunction "H22_H22") (pintype "passive+no_connect"))
    )
    (net (code "223") (name "unconnected-(J1-PadH23)") (class "Default")
      (node (ref "J1") (pin "H23") (pinfunction "H23_H23") (pintype "passive+no_connect"))
    )
    (net (code "224") (name "unconnected-(J1-PadH25)") (class "Default")
      (node (ref "J1") (pin "H25") (pinfunction "H25_H25") (pintype "passive+no_connect"))
    )
    (net (code "225") (name "unconnected-(J1-PadH26)") (class "Default")
      (node (ref "J1") (pin "H26") (pinfunction "H26_H26") (pintype "passive+no_connect"))
    )
    (net (code "226") (name "unconnected-(J1-PadH28)") (class "Default")
      (node (ref "J1") (pin "H28") (pinfunction "H28_H28") (pintype "passive+no_connect"))
    )
    (net (code "227") (name "unconnected-(J1-PadH29)") (class "Default")
      (node (ref "J1") (pin "H29") (pinfunction "H29_H29") (pintype "passive+no_connect"))
    )
    (net (code "228") (name "unconnected-(J1-PadH31)") (class "Default")
      (node (ref "J1") (pin "H31") (pinfunction "H31_H31") (pintype "passive+no_connect"))
    )
    (net (code "229") (name "unconnected-(J1-PadH32)") (class "Default")
      (node (ref "J1") (pin "H32") (pinfunction "H32_H32") (pintype "passive+no_connect"))
    )
    (net (code "230") (name "unconnected-(J1-PadH34)") (class "Default")
      (node (ref "J1") (pin "H34") (pinfunction "H34_H34") (pintype "passive+no_connect"))
    )
    (net (code "231") (name "unconnected-(J1-PadH35)") (class "Default")
      (node (ref "J1") (pin "H35") (pinfunction "H35_H35") (pintype "passive+no_connect"))
    )
    (net (code "232") (name "unconnected-(J1-PadH37)") (class "Default")
      (node (ref "J1") (pin "H37") (pinfunction "H37_H37") (pintype "passive+no_connect"))
    )
    (net (code "233") (name "unconnected-(J1-PadH38)") (class "Default")
      (node (ref "J1") (pin "H38") (pinfunction "H38_H38") (pintype "passive+no_connect"))
    )
    (net (code "234") (name "unconnected-(J1-PadJ21)") (class "Default")
      (node (ref "J1") (pin "J21") (pinfunction "J21_J21") (pintype "passive+no_connect"))
    )
    (net (code "235") (name "unconnected-(J1-PadJ22)") (class "Default")
      (node (ref "J1") (pin "J22") (pinfunction "J22_J22") (pintype "passive+no_connect"))
    )
    (net (code "236") (name "unconnected-(J1-PadJ36)") (class "Default")
      (node (ref "J1") (pin "J36") (pinfunction "J36_J36") (pintype "passive+no_connect"))
    )
    (net (code "237") (name "unconnected-(J1-PadJ37)") (class "Default")
      (node (ref "J1") (pin "J37") (pinfunction "J37_J37") (pintype "passive+no_connect"))
    )
    (net (code "238") (name "unconnected-(J1-PadK4)") (class "Default")
      (node (ref "J1") (pin "K4") (pinfunction "K4_K4") (pintype "passive+no_connect"))
    )
    (net (code "239") (name "unconnected-(J1-PadK5)") (class "Default")
      (node (ref "J1") (pin "K5") (pinfunction "K5_K5") (pintype "passive+no_connect"))
    )
    (net (code "240") (name "unconnected-(J1-PadK19)") (class "Default")
      (node (ref "J1") (pin "K19") (pinfunction "K19_K19") (pintype "passive+no_connect"))
    )
    (net (code "241") (name "unconnected-(J1-PadK20)") (class "Default")
      (node (ref "J1") (pin "K20") (pinfunction "K20_K20") (pintype "passive+no_connect"))
    )
    (net (code "242") (name "unconnected-(J1-PadK22)") (class "Default")
      (node (ref "J1") (pin "K22") (pinfunction "K22_K22") (pintype "passive+no_connect"))
    )
    (net (code "243") (name "unconnected-(J1-PadK23)") (class "Default")
      (node (ref "J1") (pin "K23") (pinfunction "K23_K23") (pintype "passive+no_connect"))
    )
    (net (code "244") (name "unconnected-(J1-PadK38)") (class "Default")
      (node (ref "J1") (pin "K38") (pinfunction "K38_K38") (pintype "passive+no_connect"))
    )
  )
)
